# ActuatorMKII_Connectors.net
KiCad netlist of a schematic drawn in Altium Designer
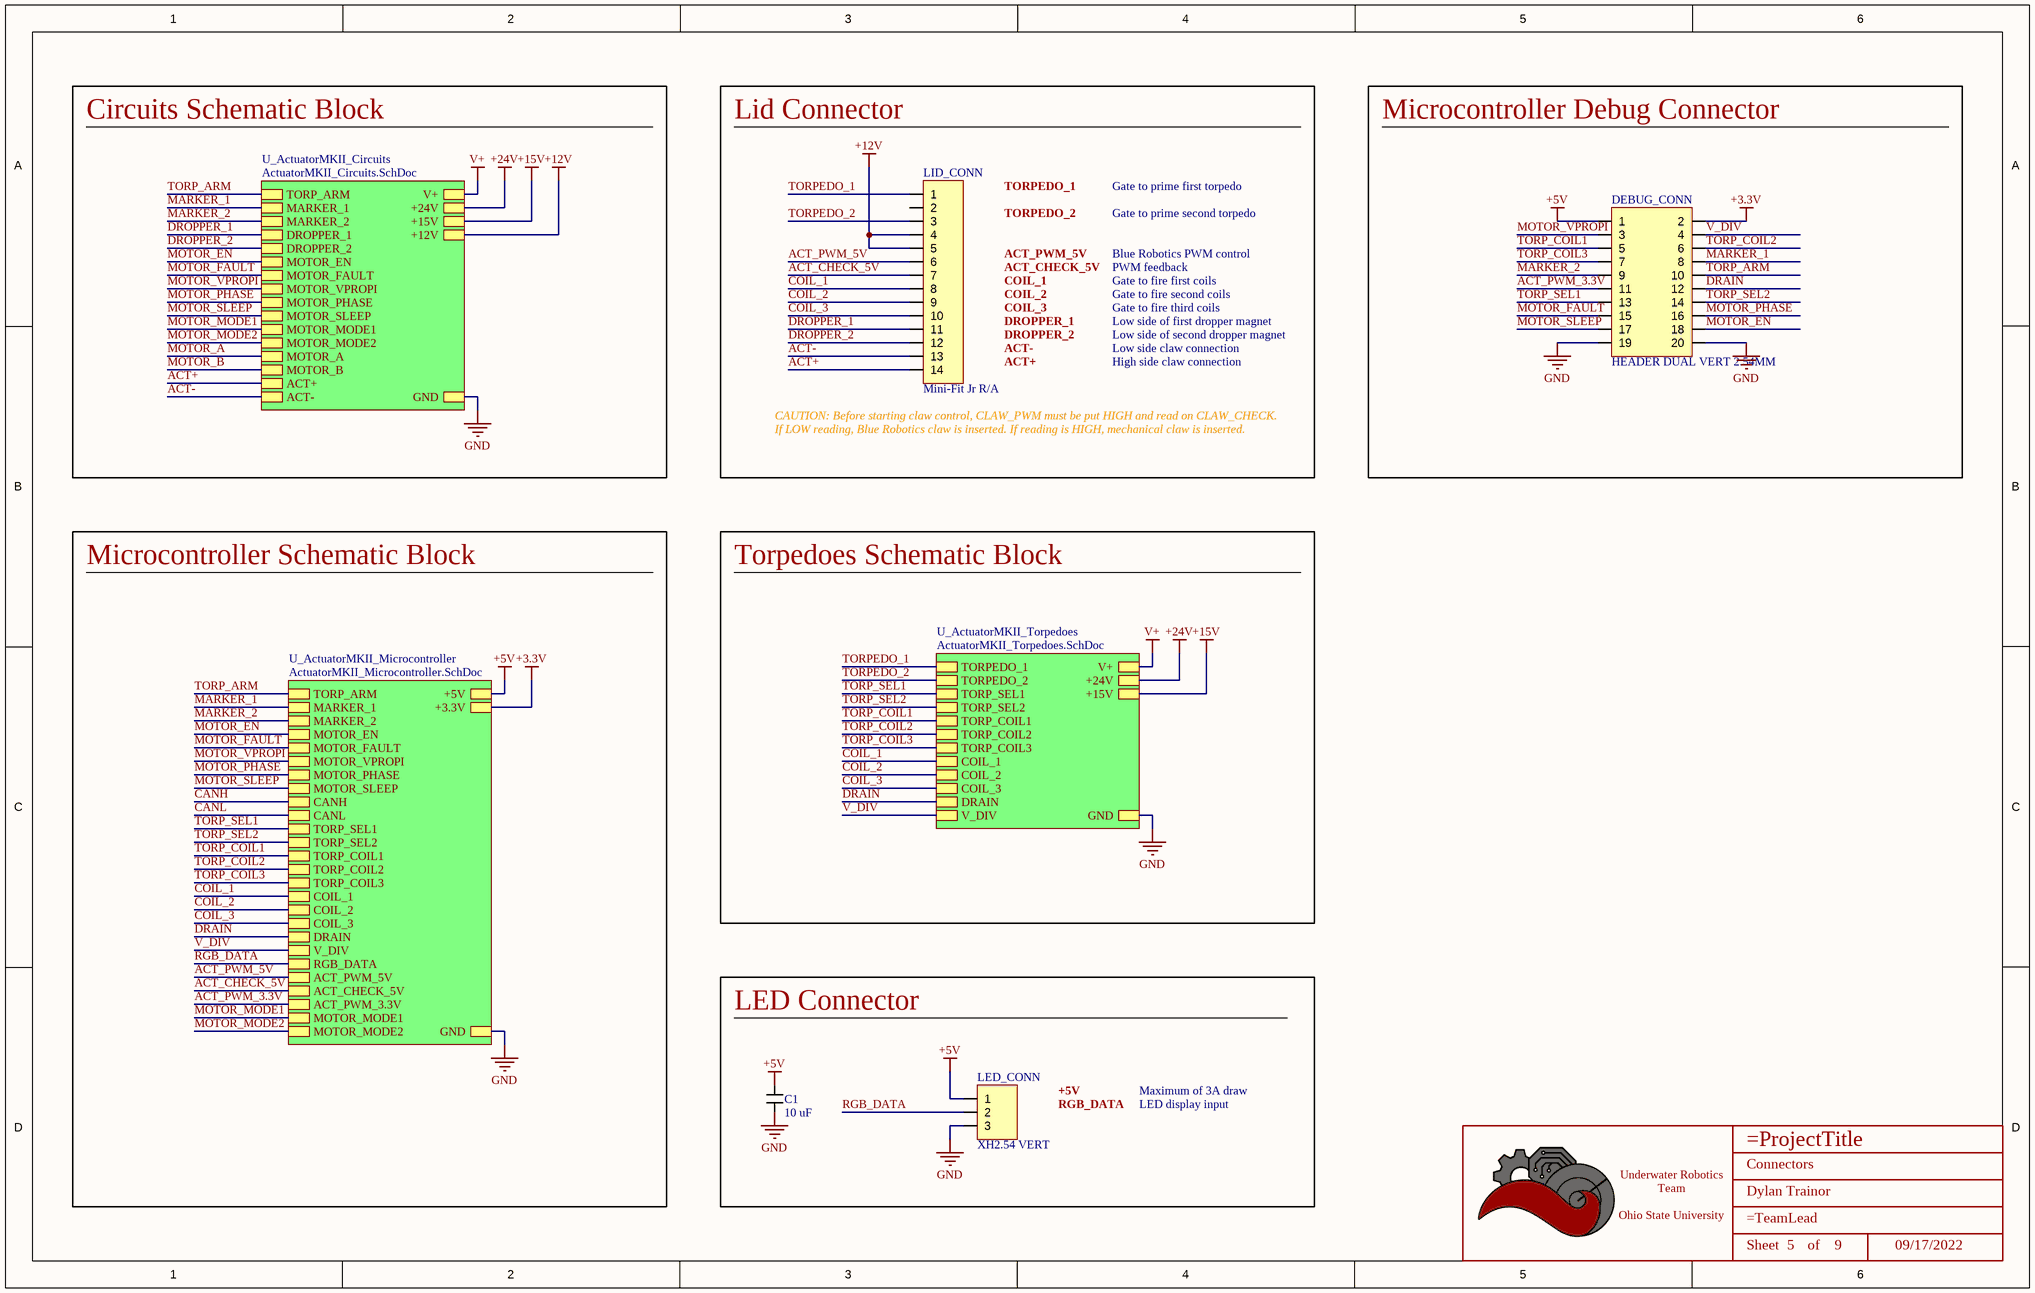
[diagram p0: ActuatorMKII_Connectors.SchDoc]

(export (version "E")
  (design (tool "Eeschema 10.0.6"))
  (components
    (comp (ref "*")
      (value "Title_Block")
      (footprint "LOGO")
      (description "UWRT Schematic Title Block Template\r\n\r\nCreated June 2021, Dylan Trainor")
      (libsource (lib "UWRT") (part "Title_Block"))
    )
    (comp (ref "C1")
      (value "10uF Ceramic 6.3V")
      (footprint "CAPACITOR_0603")
      (description "Cap 10uF 6.3V +/-20%\r\nCeramic 0603")
      (fields
        (field (name "TOLERANCE") "+/- 20%")
        (field (name "VOLTAGE") "6.3V")
        (field (name "VALUE (UF)") "10 uF")
        (field (name "MADE BY") "Flip B")
      )
      (libsource (lib "Capacitors") (part "CAPACITOR_10uF_0603"))
    )
    (comp (ref "DEBUG_CONN")
      (value "HEADER DUAL VERT 2.54MM")
      (footprint "HEADER_2x10PIN_2.54MM")
      (description "CONN HEADER VERT 20POS 2.54MM")
      (fields (field (name "MADE BY") "Tyson Nguyen"))
      (libsource (lib "Connectors") (part "HEADER_2x10PIN_2.54MM"))
    )
    (comp (ref "LED_CONN")
      (value "XH2.54 VERT")
      (footprint "CONN_JST_XH254_3POS_VERT")
      (description "JST XH 2.54mm Pitch 3 Pos Vertical")
      (fields (field (name "MANUFACTURER") "JST") (field (name "CREATED BY") "Robert P"))
      (libsource (lib "Connectors") (part "CONN_JST_XH254_3POS_VERT"))
    )
    (comp (ref "LID_CONN")
      (value "Mini-Fit Jr R/A")
      (footprint "CONN_MOLEX_MINIFIT JR_14 POS_R/A")
      (description "Molex Minifit Jr. 5569 \r\n14 Pos R/A Natural")
      (fields (field (name "MANUFACTURER") "Molex") (field (name "CREATED BY") "Flip B"))
      (libsource (lib "Connectors") (part "CONN_MOLEX_MINIFIT JR_14POS_R/A"))
    )
  )
  (nets
    (net (code "1") (name "+3.3V") (class "Default")
      (node (ref "DEBUG_CONN") (pin "2") (pinfunction "2_2") (pintype "passive"))
    )
    (net (code "2") (name "+5V") (class "Default")
      (node (ref "C1") (pin "1") (pinfunction "1_1") (pintype "passive"))
      (node (ref "DEBUG_CONN") (pin "1") (pinfunction "1_1") (pintype "passive"))
      (node (ref "LED_CONN") (pin "1") (pinfunction "1_1") (pintype "passive"))
    )
    (net (code "3") (name "+12V") (class "Default")
      (node (ref "LID_CONN") (pin "4") (pinfunction "4_4") (pintype "passive"))
      (node (ref "LID_CONN") (pin "5") (pinfunction "5_5") (pintype "passive"))
    )
    (net (code "6") (name "/ACT+") (class "Default")
      (node (ref "LID_CONN") (pin "14") (pinfunction "14_14") (pintype "passive"))
    )
    (net (code "7") (name "/ACT-") (class "Default")
      (node (ref "LID_CONN") (pin "13") (pinfunction "13_13") (pintype "passive"))
    )
    (net (code "8") (name "/ACT_CHECK_5V") (class "Default")
      (node (ref "LID_CONN") (pin "7") (pinfunction "7_7") (pintype "passive"))
    )
    (net (code "9") (name "/ACT_PWM_3.3V") (class "Default")
      (node (ref "DEBUG_CONN") (pin "11") (pinfunction "11_11") (pintype "passive"))
    )
    (net (code "10") (name "/ACT_PWM_5V") (class "Default")
      (node (ref "LID_CONN") (pin "6") (pinfunction "6_6") (pintype "passive"))
    )
    (net (code "13") (name "/COIL_1") (class "Default")
      (node (ref "LID_CONN") (pin "8") (pinfunction "8_8") (pintype "passive"))
    )
    (net (code "14") (name "/COIL_2") (class "Default")
      (node (ref "LID_CONN") (pin "9") (pinfunction "9_9") (pintype "passive"))
    )
    (net (code "15") (name "/COIL_3") (class "Default")
      (node (ref "LID_CONN") (pin "10") (pinfunction "10_10") (pintype "passive"))
    )
    (net (code "16") (name "/DRAIN") (class "Default")
      (node (ref "DEBUG_CONN") (pin "12") (pinfunction "12_12") (pintype "passive"))
    )
    (net (code "17") (name "/DROPPER_1") (class "Default")
      (node (ref "LID_CONN") (pin "11") (pinfunction "11_11") (pintype "passive"))
    )
    (net (code "18") (name "/DROPPER_2") (class "Default")
      (node (ref "LID_CONN") (pin "12") (pinfunction "12_12") (pintype "passive"))
    )
    (net (code "19") (name "/MARKER_1") (class "Default")
      (node (ref "DEBUG_CONN") (pin "8") (pinfunction "8_8") (pintype "passive"))
    )
    (net (code "20") (name "/MARKER_2") (class "Default")
      (node (ref "DEBUG_CONN") (pin "9") (pinfunction "9_9") (pintype "passive"))
    )
    (net (code "23") (name "/MOTOR_EN") (class "Default")
      (node (ref "DEBUG_CONN") (pin "18") (pinfunction "18_18") (pintype "passive"))
    )
    (net (code "24") (name "/MOTOR_FAULT") (class "Default")
      (node (ref "DEBUG_CONN") (pin "15") (pinfunction "15_15") (pintype "passive"))
    )
    (net (code "27") (name "/MOTOR_PHASE") (class "Default")
      (node (ref "DEBUG_CONN") (pin "16") (pinfunction "16_16") (pintype "passive"))
    )
    (net (code "28") (name "/MOTOR_SLEEP") (class "Default")
      (node (ref "DEBUG_CONN") (pin "17") (pinfunction "17_17") (pintype "passive"))
    )
    (net (code "29") (name "/MOTOR_VPROPI") (class "Default")
      (node (ref "DEBUG_CONN") (pin "3") (pinfunction "3_3") (pintype "passive"))
    )
    (net (code "30") (name "/RGB_DATA") (class "Default")
      (node (ref "LED_CONN") (pin "2") (pinfunction "2_2") (pintype "passive"))
    )
    (net (code "31") (name "/TORPEDO_1") (class "Default")
      (node (ref "LID_CONN") (pin "1") (pinfunction "1_1") (pintype "passive"))
    )
    (net (code "32") (name "/TORPEDO_2") (class "Default")
      (node (ref "LID_CONN") (pin "3") (pinfunction "3_3") (pintype "passive"))
    )
    (net (code "33") (name "/TORP_ARM") (class "Default")
      (node (ref "DEBUG_CONN") (pin "10") (pinfunction "10_10") (pintype "passive"))
    )
    (net (code "34") (name "/TORP_COIL1") (class "Default")
      (node (ref "DEBUG_CONN") (pin "5") (pinfunction "5_5") (pintype "passive"))
    )
    (net (code "35") (name "/TORP_COIL2") (class "Default")
      (node (ref "DEBUG_CONN") (pin "6") (pinfunction "6_6") (pintype "passive"))
    )
    (net (code "36") (name "/TORP_COIL3") (class "Default")
      (node (ref "DEBUG_CONN") (pin "7") (pinfunction "7_7") (pintype "passive"))
    )
    (net (code "37") (name "/TORP_SEL1") (class "Default")
      (node (ref "DEBUG_CONN") (pin "13") (pinfunction "13_13") (pintype "passive"))
    )
    (net (code "38") (name "/TORP_SEL2") (class "Default")
      (node (ref "DEBUG_CONN") (pin "14") (pinfunction "14_14") (pintype "passive"))
    )
    (net (code "39") (name "/V_DIV") (class "Default")
      (node (ref "DEBUG_CONN") (pin "4") (pinfunction "4_4") (pintype "passive"))
    )
    (net (code "40") (name "GND") (class "Default")
      (node (ref "C1") (pin "2") (pinfunction "2_2") (pintype "passive"))
      (node (ref "DEBUG_CONN") (pin "19") (pinfunction "19_19") (pintype "passive"))
      (node (ref "DEBUG_CONN") (pin "20") (pinfunction "20_20") (pintype "passive"))
      (node (ref "LED_CONN") (pin "3") (pinfunction "3_3") (pintype "passive"))
    )
    (net (code "42") (name "unconnected-(LID_CONN-Pad2)") (class "Default")
      (node (ref "LID_CONN") (pin "2") (pinfunction "2_2") (pintype "passive"))
    )
  )
)
